# 200_FLASH_AND_UART.net
KiCad netlist of a schematic drawn in Altium Designer
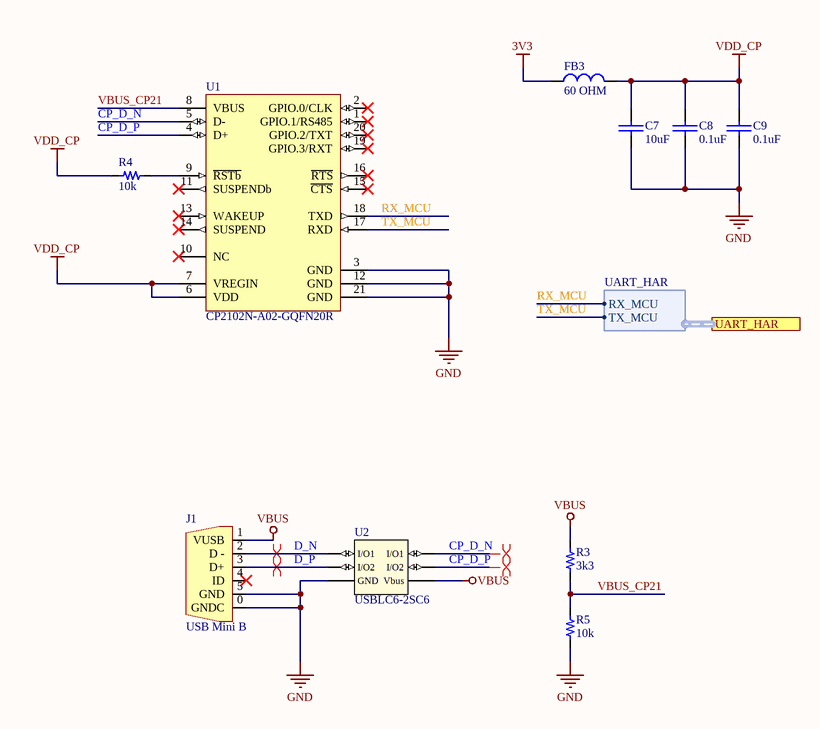
[diagram p0: 200_FLASH_AND_UART.SchDoc]

(export (version "E")
  (design (tool "Eeschema 10.0.6"))
  (components
    (comp (ref "C7")
      (value "10uF")
      (footprint "0603_cap")
      (description "10V 10uF X5R ±10% 0603 Multilayer Ceramic Capacitors MLCC - SMD/SMT ROHS")
      (fields
        (field (name "MANUFACTURER") "CCTC")
        (field (name "MANUFACTURER PART NUMBER") "TCC0603X5R106K100CT")
      )
      (libsource (lib "shared_lib") (part "Cap_10uF_0603_10V"))
    )
    (comp (ref "C8")
      (value "0.1uF")
      (footprint "0603_cap")
      (description "50V 100nF Y5V -20%~+80% 0603 Multilayer Ceramic Capacitors MLCC - SMD/SMT ROHS")
      (fields
        (field (name "MANUFACTURER") "Walsin Tech Corp")
        (field (name "MANUFACTURER PART NUMBER") "0603F104Z500CT")
      )
      (libsource (lib "shared_lib") (part "Cap_0.1uF_0603_50V"))
    )
    (comp (ref "C9")
      (value "0.1uF")
      (footprint "0603_cap")
      (description "50V 100nF Y5V -20%~+80% 0603 Multilayer Ceramic Capacitors MLCC - SMD/SMT ROHS")
      (fields
        (field (name "MANUFACTURER") "Walsin Tech Corp")
        (field (name "MANUFACTURER PART NUMBER") "0603F104Z500CT")
      )
      (libsource (lib "shared_lib") (part "Cap_0.1uF_0603_50V"))
    )
    (comp (ref "FB3")
      (value "60 OHM")
      (footprint "0603_fb")
      (description "2A 1 100mΩ 60Ω@100MHz ±25% 0603 Ferrite Beads ROHS")
      (fields
        (field (name "MANUFACTURER") "TAI-TECH")
        (field (name "MANUFACTURER PART NUMBER") "HCB1608KF-600T20")
      )
      (libsource (lib "shared_lib") (part "FB_60_0603_2A"))
    )
    (comp (ref "J1")
      (value "USB Mini B")
      (footprint "CON_5x1_SMD_miniUSB_B")
      (description "CONN RCPT USB2.0 MINI B SMD R/A")
      (fields
        (field (name "MANUFACTURER PART NUMBER") "KH-MINI-SMT-5P-Cu")
        (field (name "MANUFACTURER") "EDAC Inc.")
      )
      (libsource (lib "shared_lib") (part "Con_Mini_USB_B"))
    )
    (comp (ref "R3")
      (value "3k3")
      (footprint "0603_res")
      (description "RES SMD 3k3 OHM 5% 1/10W 0603")
      (fields
        (field (name "MANUFACTURER") "FOJAN")
        (field (name "MANUFACTURER PART NUMBER") "FRC0603J332 TS")
      )
      (libsource (lib "shared_lib") (part "Res_3k3_0603_1/10W"))
    )
    (comp (ref "R4")
      (value "10k")
      (footprint "0603_res")
      (description "RES SMD 10k OHM 5% 1/10W 0603")
      (fields (field (name "MANUFACTURER") "FOJAN") (field (name "MANUFACTURER PART NUMBER") "FRC0603J103TS"))
      (libsource (lib "shared_lib") (part "Res_10k_0603_1/10W"))
    )
    (comp (ref "R5")
      (value "10k")
      (footprint "0603_res")
      (description "RES SMD 10k OHM 5% 1/10W 0603")
      (fields (field (name "MANUFACTURER") "FOJAN") (field (name "MANUFACTURER PART NUMBER") "FRC0603J103TS"))
      (libsource (lib "shared_lib") (part "Res_10k_0603_1/10W"))
    )
    (comp (ref "U1")
      (value "CP2102N-A02-GQFN20R")
      (footprint "WFQFN_20_EP_3X3MM")
      (description "IC USB TO UART BRIDGE QFN20")
      (fields (field (name "MANUFACTURER") "Silicon Labs"))
      (libsource (lib "shared_lib") (part "IC_SGL_USB2UART-BRIDGE_20QFN"))
    )
    (comp (ref "U2")
      (value "USBLC6-2SC6")
      (footprint "SOT_23_6")
      (description "TVS DIODE 5.25V 17V SOT23-6")
      (fields (field (name "MANUFACTURER") "STMicroelectronics"))
      (libsource (lib "shared_lib") (part "TVS_5.25V_2CH_SOT_23_6"))
    )
  )
  (nets
    (net (code "2") (name "/CP_D_N") (class "Default")
      (node (ref "U1") (pin "5") (pinfunction "D-_5") (pintype "bidirectional"))
      (node (ref "U2") (pin "6") (pinfunction "I/O1_6") (pintype "bidirectional"))
    )
    (net (code "3") (name "/CP_D_P") (class "Default")
      (node (ref "U1") (pin "4") (pinfunction "D+_4") (pintype "bidirectional"))
      (node (ref "U2") (pin "4") (pinfunction "I/O2_4") (pintype "bidirectional"))
    )
    (net (code "4") (name "/D_N") (class "Default")
      (node (ref "J1") (pin "2") (pinfunction "D_-_2") (pintype "passive"))
      (node (ref "U2") (pin "1") (pinfunction "I/O1_1") (pintype "bidirectional"))
    )
    (net (code "5") (name "/D_P") (class "Default")
      (node (ref "J1") (pin "3") (pinfunction "D+_3") (pintype "passive"))
      (node (ref "U2") (pin "3") (pinfunction "I/O2_3") (pintype "bidirectional"))
    )
    (net (code "6") (name "/RX_MCU") (class "Default")
      (node (ref "U1") (pin "18") (pinfunction "TXD_18") (pintype "output"))
    )
    (net (code "7") (name "/TX_MCU") (class "Default")
      (node (ref "U1") (pin "17") (pinfunction "RXD_17") (pintype "input"))
    )
    (net (code "8") (name "/VBUS_CP21") (class "Default")
      (node (ref "R3") (pin "1") (pinfunction "1_1") (pintype "passive"))
      (node (ref "R5") (pin "2") (pinfunction "2_2") (pintype "passive"))
      (node (ref "U1") (pin "8") (pinfunction "VBUS_8") (pintype "power_in"))
    )
    (net (code "10") (name "3V3") (class "Default")
      (node (ref "FB3") (pin "1") (pinfunction "1_1") (pintype "passive"))
    )
    (net (code "11") (name "GND") (class "Default")
      (node (ref "C7") (pin "2") (pinfunction "2_2") (pintype "passive"))
      (node (ref "C8") (pin "2") (pinfunction "2_2") (pintype "passive"))
      (node (ref "C9") (pin "2") (pinfunction "2_2") (pintype "passive"))
      (node (ref "J1") (pin "0") (pinfunction "GNDC_0") (pintype "passive"))
      (node (ref "J1") (pin "5") (pinfunction "GND_5") (pintype "passive"))
      (node (ref "R5") (pin "1") (pinfunction "1_1") (pintype "passive"))
      (node (ref "U1") (pin "12") (pinfunction "GND_12") (pintype "power_in"))
      (node (ref "U1") (pin "21") (pinfunction "GND_21") (pintype "power_in"))
      (node (ref "U1") (pin "3") (pinfunction "GND_3") (pintype "power_in"))
      (node (ref "U2") (pin "2") (pinfunction "GND_2") (pintype "power_in"))
    )
    (net (code "12") (name "Net-(U1-~{RSTb})") (class "Default")
      (node (ref "R4") (pin "1") (pinfunction "1_1") (pintype "passive"))
      (node (ref "U1") (pin "9") (pinfunction "~{RSTb}_9") (pintype "input"))
    )
    (net (code "13") (name "VBUS") (class "Default")
      (node (ref "J1") (pin "1") (pinfunction "VUSB_1") (pintype "passive"))
      (node (ref "R3") (pin "2") (pinfunction "2_2") (pintype "passive"))
      (node (ref "U2") (pin "5") (pinfunction "Vbus_5") (pintype "power_in"))
    )
    (net (code "14") (name "VDD_CP") (class "Default")
      (node (ref "C7") (pin "1") (pinfunction "1_1") (pintype "passive"))
      (node (ref "C8") (pin "1") (pinfunction "1_1") (pintype "passive"))
      (node (ref "C9") (pin "1") (pinfunction "1_1") (pintype "passive"))
      (node (ref "FB3") (pin "2") (pinfunction "2_2") (pintype "passive"))
      (node (ref "R4") (pin "2") (pinfunction "2_2") (pintype "passive"))
      (node (ref "U1") (pin "6") (pinfunction "VDD_6") (pintype "power_in"))
      (node (ref "U1") (pin "7") (pinfunction "VREGIN_7") (pintype "power_in"))
    )
    (net (code "15") (name "unconnected-(J1-ID-Pad4)") (class "Default")
      (node (ref "J1") (pin "4") (pinfunction "ID_4") (pintype "passive+no_connect"))
    )
    (net (code "16") (name "unconnected-(U1-GPIO.0{slash}CLK-Pad2)") (class "Default")
      (node (ref "U1") (pin "2") (pinfunction "GPIO.0/CLK_2") (pintype "bidirectional+no_connect"))
    )
    (net (code "17") (name "unconnected-(U1-GPIO.1{slash}RS485-Pad1)") (class "Default")
      (node (ref "U1") (pin "1") (pinfunction "GPIO.1/RS485_1") (pintype "bidirectional+no_connect"))
    )
    (net (code "18") (name "unconnected-(U1-GPIO.2{slash}TXT-Pad20)") (class "Default")
      (node (ref "U1") (pin "20") (pinfunction "GPIO.2/TXT_20") (pintype "bidirectional+no_connect"))
    )
    (net (code "19") (name "unconnected-(U1-GPIO.3{slash}RXT-Pad19)") (class "Default")
      (node (ref "U1") (pin "19") (pinfunction "GPIO.3/RXT_19") (pintype "bidirectional+no_connect"))
    )
    (net (code "20") (name "unconnected-(U1-NC-Pad10)") (class "Default")
      (node (ref "U1") (pin "10") (pinfunction "NC_10") (pintype "passive+no_connect"))
    )
    (net (code "21") (name "unconnected-(U1-SUSPEND-Pad14)") (class "Default")
      (node (ref "U1") (pin "14") (pinfunction "SUSPEND_14") (pintype "output+no_connect"))
    )
    (net (code "22") (name "unconnected-(U1-SUSPENDb-Pad11)") (class "Default")
      (node (ref "U1") (pin "11") (pinfunction "SUSPENDb_11") (pintype "output+no_connect"))
    )
    (net (code "23") (name "unconnected-(U1-WAKEUP-Pad13)") (class "Default")
      (node (ref "U1") (pin "13") (pinfunction "WAKEUP_13") (pintype "input+no_connect"))
    )
    (net (code "24") (name "unconnected-(U1-~{CTS}-Pad15)") (class "Default")
      (node (ref "U1") (pin "15") (pinfunction "~{CTS}_15") (pintype "input+no_connect"))
    )
    (net (code "25") (name "unconnected-(U1-~{RTS}-Pad16)") (class "Default")
      (node (ref "U1") (pin "16") (pinfunction "~{RTS}_16") (pintype "output+no_connect"))
    )
  )
)
